# SWD_BOOT.net
KiCad netlist of a schematic drawn in Altium Designer
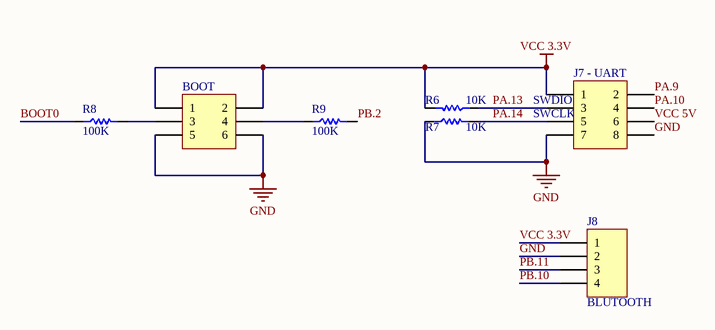
[diagram p0: SWD & BOOT.SchDoc]

(export (version "E")
  (design (tool "Eeschema 10.0.6"))
  (components
    (comp (ref "BOOT")
      (value "Header 3X2")
      (footprint "HDR2X3")
      (description "Header, 3-Pin, Dual row")
      (fields (field (name "PUBLISHER") "Altium Limited"))
      (libsource (lib "Miscellaneous Connectors") (part "Header 3X2"))
    )
    (comp (ref "J7 - UART")
      (value "Header 4X2")
      (footprint "HDR2X4")
      (description "Header, 4-Pin, Dual row")
      (fields (field (name "PUBLISHER") "Altium Limited"))
      (libsource (lib "Miscellaneous Connectors") (part "Header 4X2"))
    )
    (comp (ref "J8")
      (value "BLUTOOTH")
      (footprint "HDR1X4")
      (description "Header, 4-Pin")
      (fields (field (name "PUBLISHER") "Altium Limited"))
      (libsource (lib "Miscellaneous Connectors") (part "Header 4"))
    )
    (comp (ref "R6")
      (value "10K")
      (footprint "SMD_RES_0805")
      (description "Resistor")
      (fields (field (name "TOLERANCE") "5%") (field (name "POWER") "1/8 W"))
      (libsource (lib "DDEmS Library") (part "Resistor"))
    )
    (comp (ref "R7")
      (value "10K")
      (footprint "SMD_RES_0805")
      (description "Resistor")
      (fields (field (name "TOLERANCE") "5%") (field (name "POWER") "1/8 W"))
      (libsource (lib "DDEmS Library") (part "Resistor"))
    )
    (comp (ref "R8")
      (value "100K")
      (footprint "SMD_RES_0805")
      (description "Resistor")
      (fields (field (name "TOLERANCE") "5%") (field (name "POWER") "1/8 W"))
      (libsource (lib "DDEmS Library") (part "Resistor"))
    )
    (comp (ref "R9")
      (value "100K")
      (footprint "SMD_RES_0805")
      (description "Resistor")
      (fields (field (name "TOLERANCE") "5%") (field (name "POWER") "1/8 W"))
      (libsource (lib "DDEmS Library") (part "Resistor"))
    )
  )
  (nets
    (net (code "1") (name "/BOOT0") (class "Default")
      (node (ref "R8") (pin "1") (pinfunction "1_1") (pintype "passive"))
    )
    (net (code "2") (name "/PA.9") (class "Default")
      (node (ref "J7 - UART") (pin "2") (pinfunction "2_2") (pintype "passive"))
    )
    (net (code "3") (name "/PA.10") (class "Default")
      (node (ref "J7 - UART") (pin "4") (pinfunction "4_4") (pintype "passive"))
    )
    (net (code "4") (name "/PA.13") (class "Default")
      (node (ref "J7 - UART") (pin "3") (pinfunction "3_3") (pintype "passive"))
      (node (ref "R6") (pin "1") (pinfunction "1_1") (pintype "passive"))
    )
    (net (code "5") (name "/PA.14") (class "Default")
      (node (ref "J7 - UART") (pin "5") (pinfunction "5_5") (pintype "passive"))
      (node (ref "R7") (pin "2") (pinfunction "2_2") (pintype "passive"))
    )
    (net (code "6") (name "/PB.2") (class "Default")
      (node (ref "R9") (pin "2") (pinfunction "2_2") (pintype "passive"))
    )
    (net (code "7") (name "/PB.10") (class "Default")
      (node (ref "J8") (pin "4") (pinfunction "4_4") (pintype "passive"))
    )
    (net (code "8") (name "/PB.11") (class "Default")
      (node (ref "J8") (pin "3") (pinfunction "3_3") (pintype "passive"))
    )
    (net (code "9") (name "/VCC 5V") (class "Default")
      (node (ref "J7 - UART") (pin "6") (pinfunction "6_6") (pintype "passive"))
    )
    (net (code "10") (name "GND") (class "Default")
      (node (ref "BOOT") (pin "5") (pinfunction "5_5") (pintype "passive"))
      (node (ref "BOOT") (pin "6") (pinfunction "6_6") (pintype "passive"))
      (node (ref "J7 - UART") (pin "7") (pinfunction "7_7") (pintype "passive"))
      (node (ref "J7 - UART") (pin "8") (pinfunction "8_8") (pintype "passive"))
      (node (ref "J8") (pin "2") (pinfunction "2_2") (pintype "passive"))
      (node (ref "R7") (pin "1") (pinfunction "1_1") (pintype "passive"))
    )
    (net (code "11") (name "Net-(BOOT-Pad3)") (class "Default")
      (node (ref "BOOT") (pin "3") (pinfunction "3_3") (pintype "passive"))
      (node (ref "R8") (pin "2") (pinfunction "2_2") (pintype "passive"))
    )
    (net (code "12") (name "Net-(BOOT-Pad4)") (class "Default")
      (node (ref "BOOT") (pin "4") (pinfunction "4_4") (pintype "passive"))
      (node (ref "R9") (pin "1") (pinfunction "1_1") (pintype "passive"))
    )
    (net (code "13") (name "VCC 3.3V") (class "Default")
      (node (ref "BOOT") (pin "1") (pinfunction "1_1") (pintype "passive"))
      (node (ref "BOOT") (pin "2") (pinfunction "2_2") (pintype "passive"))
      (node (ref "J7 - UART") (pin "1") (pinfunction "1_1") (pintype "passive"))
      (node (ref "J8") (pin "1") (pinfunction "1_1") (pintype "passive"))
      (node (ref "R6") (pin "2") (pinfunction "2_2") (pintype "passive"))
    )
  )
)
